# darwin-radio.net
KiCad netlist of a schematic drawn in EAGLE
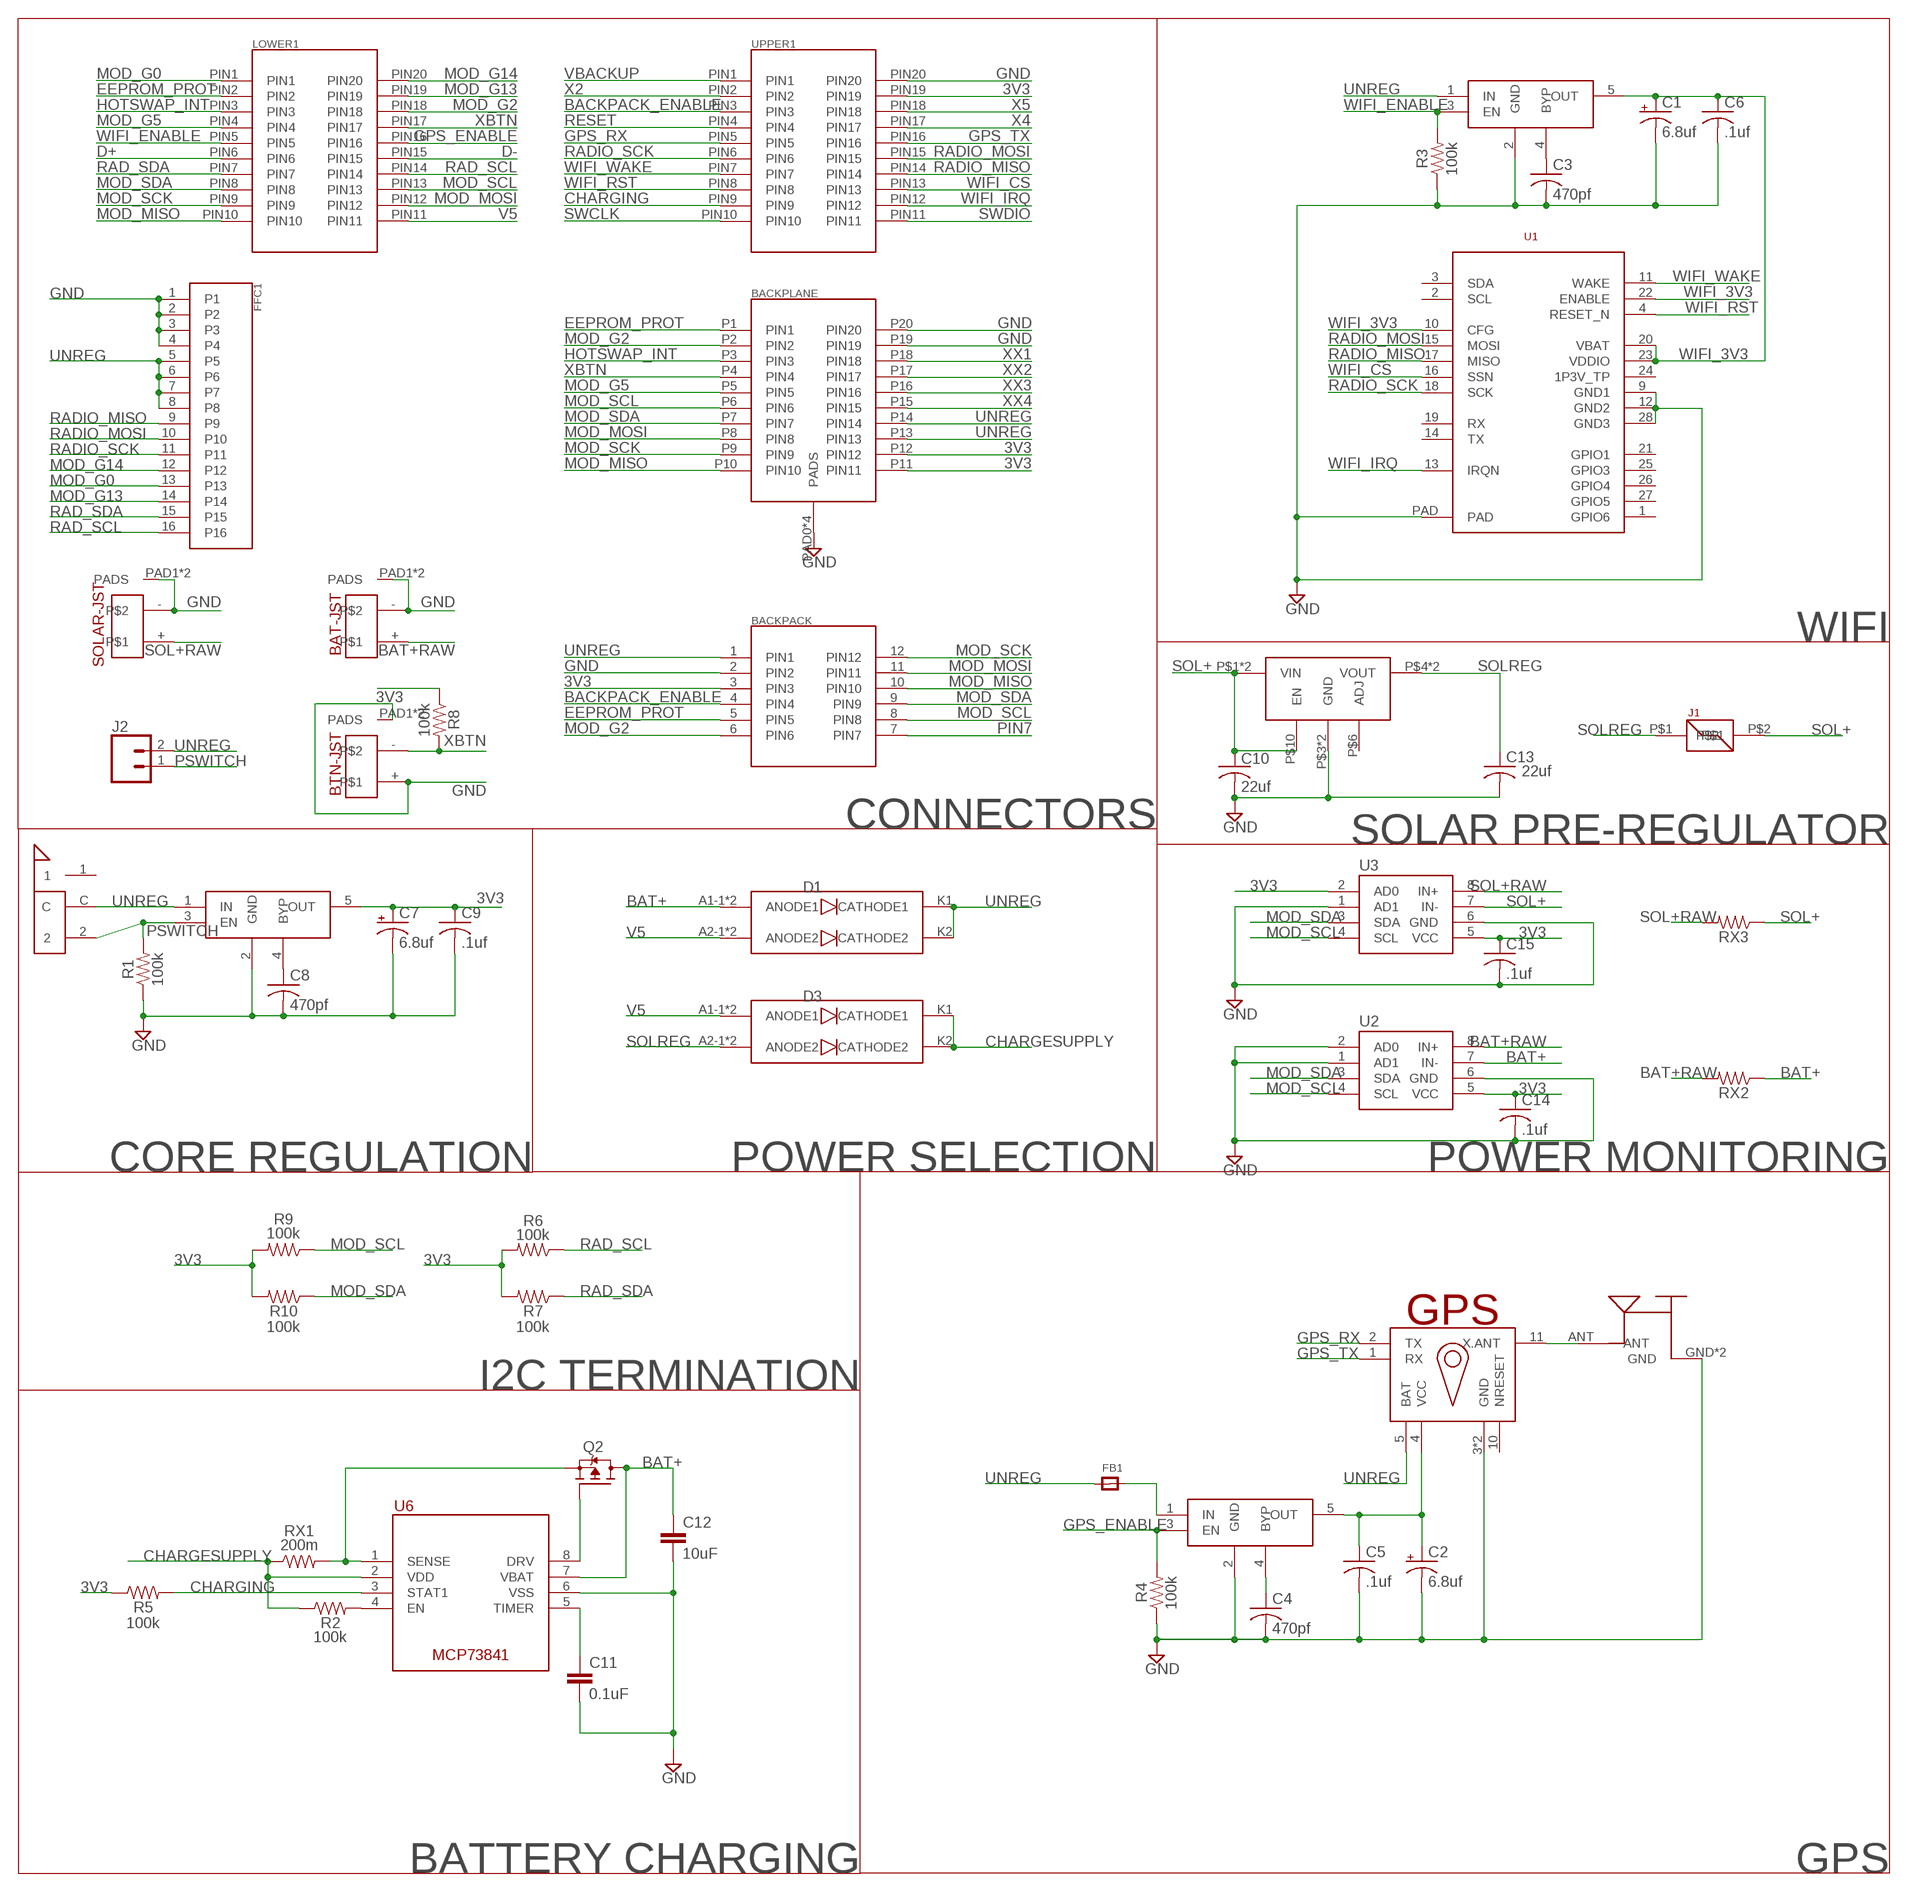
[diagram p0: schematic, sheet 1]

(export (version "E")
  (design (tool "Eeschema 10.0.6"))
  (components
    (comp (ref "BACKPACK")
      (value "2X6-HEADERSDS")
      (footprint "eagle-import:12PH")
      (libsource (lib "eagle-import") (part "2X6-HEADERSDS"))
    )
    (comp (ref "BACKPLANE")
      (value "M55-6102042R")
      (footprint "eagle-import:M55-6102042R")
      (libsource (lib "eagle-import") (part "M55-6102042R"))
    )
    (comp (ref "BAT-JST")
      (value "B2B-PH-SM4-TB")
      (footprint "eagle-import:B2B-PH-SM4-TB")
      (libsource (lib "eagle-import") (part "B2B-PH-SM4-TB"))
    )
    (comp (ref "BTN-JST")
      (value "B2B-PH-SM4-TB")
      (footprint "eagle-import:B2B-PH-SM4-TB")
      (libsource (lib "eagle-import") (part "B2B-PH-SM4-TB"))
    )
    (comp (ref "C1")
      (value "6.8uf")
      (footprint "eagle-import:A_3216-18R")
      (libsource (lib "eagle-import") (part "CPOL-USA/3216-18R"))
    )
    (comp (ref "C2")
      (value "6.8uf")
      (footprint "eagle-import:A_3216-18R")
      (libsource (lib "eagle-import") (part "CPOL-USA/3216-18R"))
    )
    (comp (ref "C3")
      (value "470pf")
      (footprint "eagle-import:C0603K")
      (libsource (lib "eagle-import") (part "C-USC0603K"))
    )
    (comp (ref "C4")
      (value "470pf")
      (footprint "eagle-import:C0603K")
      (libsource (lib "eagle-import") (part "C-USC0603K"))
    )
    (comp (ref "C5")
      (value ".1uf")
      (footprint "eagle-import:C0603K")
      (libsource (lib "eagle-import") (part "C-USC0603K"))
    )
    (comp (ref "C6")
      (value ".1uf")
      (footprint "eagle-import:C0603K")
      (libsource (lib "eagle-import") (part "C-USC0603K"))
    )
    (comp (ref "C7")
      (value "6.8uf")
      (footprint "eagle-import:A_3216-18R")
      (libsource (lib "eagle-import") (part "CPOL-USA/3216-18R"))
    )
    (comp (ref "C8")
      (value "470pf")
      (footprint "eagle-import:C0603K")
      (libsource (lib "eagle-import") (part "C-USC0603K"))
    )
    (comp (ref "C9")
      (value ".1uf")
      (footprint "eagle-import:C0603K")
      (libsource (lib "eagle-import") (part "C-USC0603K"))
    )
    (comp (ref "C10")
      (value "22uf")
      (footprint "eagle-import:C0603K")
      (libsource (lib "eagle-import") (part "C-USC0603K"))
    )
    (comp (ref "C11")
      (value "0.1uF")
      (footprint "eagle-import:0603")
      (libsource (lib "eagle-import") (part "0.1UF-0603-25V-(+80/-20%)"))
    )
    (comp (ref "C12")
      (value "10uF")
      (footprint "eagle-import:0603")
      (libsource (lib "eagle-import") (part "10UF-0603-6.3V-20%"))
    )
    (comp (ref "C13")
      (value "22uf")
      (footprint "eagle-import:C0603K")
      (libsource (lib "eagle-import") (part "C-USC0603K"))
    )
    (comp (ref "C14")
      (value ".1uf")
      (footprint "eagle-import:C0603K")
      (libsource (lib "eagle-import") (part "C-USC0603K"))
    )
    (comp (ref "C15")
      (value ".1uf")
      (footprint "eagle-import:C0603K")
      (libsource (lib "eagle-import") (part "C-USC0603K"))
    )
    (comp (ref "D1")
      (value "V10KL45DUHM3/H")
      (footprint "eagle-import:V10KL45DUHM3_H")
      (libsource (lib "eagle-import") (part "V10KL45DUHM3/H"))
    )
    (comp (ref "D3")
      (value "V10KL45DUHM3/H")
      (footprint "eagle-import:V10KL45DUHM3_H")
      (libsource (lib "eagle-import") (part "V10KL45DUHM3/H"))
    )
    (comp (ref "FB1")
      (value "FERRITE0805")
      (footprint "eagle-import:0805")
      (libsource (lib "eagle-import") (part "FERRITE0805"))
    )
    (comp (ref "FFC1")
      (value "505110-1692")
      (footprint "eagle-import:505110-1692")
      (libsource (lib "eagle-import") (part "505110-1692"))
    )
    (comp (ref "J1")
      (value "S1911-46R")
      (footprint "eagle-import:S1911-46R")
      (libsource (lib "eagle-import") (part "S1911-46R"))
    )
    (comp (ref "J2")
      (value "CONN_02LOCK_LONGPADS")
      (footprint "eagle-import:1X02_LOCK_LONGPADS")
      (libsource (lib "eagle-import") (part "CONN_02LOCK_LONGPADS"))
    )
    (comp (ref "LOWER1")
      (value "MOLEX-15-91-2200")
      (footprint "eagle-import:20PH")
      (libsource (lib "eagle-import") (part "MOLEX-15-91-2200"))
    )
    (comp (ref "Q2")
      (value "NDS8434")
      (footprint "eagle-import:SO08-IRF")
      (libsource (lib "eagle-import") (part "NDS8434"))
    )
    (comp (ref "R1")
      (value "100k")
      (footprint "eagle-import:0603")
      (libsource (lib "eagle-import") (part "100KOHM-0603-1/10W-1%"))
    )
    (comp (ref "R2")
      (value "100k")
      (footprint "eagle-import:0603")
      (libsource (lib "eagle-import") (part "100KOHM-0603-1/10W-1%"))
    )
    (comp (ref "R3")
      (value "100k")
      (footprint "eagle-import:0603")
      (libsource (lib "eagle-import") (part "100KOHM-0603-1/10W-1%"))
    )
    (comp (ref "R4")
      (value "100k")
      (footprint "eagle-import:0603")
      (libsource (lib "eagle-import") (part "100KOHM-0603-1/10W-1%"))
    )
    (comp (ref "R5")
      (value "100k")
      (footprint "eagle-import:0603")
      (libsource (lib "eagle-import") (part "100KOHM-0603-1/10W-1%"))
    )
    (comp (ref "R6")
      (value "100k")
      (footprint "eagle-import:0603")
      (libsource (lib "eagle-import") (part "100KOHM-0603-1/10W-1%"))
    )
    (comp (ref "R7")
      (value "100k")
      (footprint "eagle-import:0603")
      (libsource (lib "eagle-import") (part "100KOHM-0603-1/10W-1%"))
    )
    (comp (ref "R8")
      (value "100k")
      (footprint "eagle-import:0603")
      (libsource (lib "eagle-import") (part "100KOHM-0603-1/10W-1%"))
    )
    (comp (ref "R9")
      (value "100k")
      (footprint "eagle-import:0603")
      (libsource (lib "eagle-import") (part "100KOHM-0603-1/10W-1%"))
    )
    (comp (ref "R10")
      (value "100k")
      (footprint "eagle-import:0603")
      (libsource (lib "eagle-import") (part "100KOHM-0603-1/10W-1%"))
    )
    (comp (ref "REG1")
      (value "V78E06-1000-SMT-TR")
      (footprint "eagle-import:V78E06-1000-SMT-TR")
      (libsource (lib "eagle-import") (part "V78E06-1000-SMT-TR"))
    )
    (comp (ref "RX1")
      (value "200m")
      (footprint "eagle-import:R2512")
      (libsource (lib "eagle-import") (part "R-US_R2512"))
    )
    (comp (ref "RX2")
      (value "100M")
      (footprint "eagle-import:R2512")
      (libsource (lib "eagle-import") (part "R-US_R2512"))
    )
    (comp (ref "RX3")
      (value "100M")
      (footprint "eagle-import:R2512")
      (libsource (lib "eagle-import") (part "R-US_R2512"))
    )
    (comp (ref "SOLAR-JST")
      (value "B2B-PH-SM4-TB")
      (footprint "eagle-import:B2B-PH-SM4-TB")
      (libsource (lib "eagle-import") (part "B2B-PH-SM4-TB"))
    )
    (comp (ref "U$1")
      (value "FGPMMOPA6HL80")
      (footprint "eagle-import:L80-M39")
      (libsource (lib "eagle-import") (part "FGPMMOPA6HL80"))
    )
    (comp (ref "U$2")
      (value "MIC5219-3.3YM5-TR")
      (footprint "eagle-import:SOT95P280X145-5")
      (libsource (lib "eagle-import") (part "MIC5219-3.3YM5-TR"))
    )
    (comp (ref "U$3")
      (value "MIC5219-3.3YM5-TR")
      (footprint "eagle-import:SOT95P280X145-5")
      (libsource (lib "eagle-import") (part "MIC5219-3.3YM5-TR"))
    )
    (comp (ref "U$4")
      (value "MIC5219-3.3YM5-TR")
      (footprint "eagle-import:SOT95P280X145-5")
      (libsource (lib "eagle-import") (part "MIC5219-3.3YM5-TR"))
    )
    (comp (ref "U$5")
      (value "SSAJ110100")
      (footprint "eagle-import:SSAJ110100")
      (libsource (lib "eagle-import") (part "SSAJ110100"))
    )
    (comp (ref "U$11")
      (value "2337019-1")
      (footprint "eagle-import:2337019-1")
      (libsource (lib "eagle-import") (part "2337019-1"))
    )
    (comp (ref "U1")
      (value "ATWINC")
      (footprint "eagle-import:ATWINC")
      (libsource (lib "eagle-import") (part "ATWINC"))
    )
    (comp (ref "U2")
      (value "INA219")
      (footprint "eagle-import:SOIC127P599X175-8N")
      (libsource (lib "eagle-import") (part "INA219"))
    )
    (comp (ref "U3")
      (value "INA219")
      (footprint "eagle-import:SOIC127P599X175-8N")
      (libsource (lib "eagle-import") (part "INA219"))
    )
    (comp (ref "U6")
      (value "MCP7384X")
      (footprint "eagle-import:SOP65P490X110-8")
      (libsource (lib "eagle-import") (part "MCP7384X"))
    )
    (comp (ref "UPPER1")
      (value "MOLEX-15-91-2200")
      (footprint "eagle-import:20PH")
      (libsource (lib "eagle-import") (part "MOLEX-15-91-2200"))
    )
  )
  (nets
    (net (code "1") (name "/3V3") (class "Default")
      (node (ref "BACKPACK") (pin "3") (pinfunction "PIN3_3") (pintype "bidirectional"))
      (node (ref "BACKPLANE") (pin "P11") (pinfunction "PIN11_P11") (pintype "bidirectional"))
      (node (ref "BACKPLANE") (pin "P12") (pinfunction "PIN12_P12") (pintype "bidirectional"))
      (node (ref "C14") (pin "1") (pinfunction "1_1") (pintype "passive"))
      (node (ref "C15") (pin "1") (pinfunction "1_1") (pintype "passive"))
      (node (ref "C7") (pin "+") (pinfunction "+_+") (pintype "passive"))
      (node (ref "C9") (pin "1") (pinfunction "1_1") (pintype "passive"))
      (node (ref "R10") (pin "2") (pinfunction "2_2") (pintype "passive"))
      (node (ref "R5") (pin "1") (pinfunction "1_1") (pintype "passive"))
      (node (ref "R6") (pin "2") (pinfunction "2_2") (pintype "passive"))
      (node (ref "R7") (pin "2") (pinfunction "2_2") (pintype "passive"))
      (node (ref "R8") (pin "1") (pinfunction "1_1") (pintype "passive"))
      (node (ref "R9") (pin "2") (pinfunction "2_2") (pintype "passive"))
      (node (ref "U$4") (pin "5") (pinfunction "OUT_5") (pintype "bidirectional"))
      (node (ref "U2") (pin "5") (pinfunction "VCC_5") (pintype "bidirectional"))
      (node (ref "U3") (pin "2") (pinfunction "AD0_2") (pintype "bidirectional"))
      (node (ref "U3") (pin "5") (pinfunction "VCC_5") (pintype "bidirectional"))
      (node (ref "UPPER1") (pin "PIN19") (pinfunction "PIN19_PIN19") (pintype "bidirectional"))
    )
    (net (code "2") (name "/BACKPACK_ENABLE") (class "Default")
      (node (ref "BACKPACK") (pin "4") (pinfunction "PIN4_4") (pintype "bidirectional"))
      (node (ref "UPPER1") (pin "PIN3") (pinfunction "PIN3_PIN3") (pintype "bidirectional"))
    )
    (net (code "3") (name "/BAT+") (class "Default")
      (node (ref "C12") (pin "1") (pinfunction "1_1") (pintype "passive"))
      (node (ref "D1") (pin "A1-1") (pinfunction "ANODE1_A1-1") (pintype "bidirectional"))
      (node (ref "D1") (pin "A1-2") (pinfunction "ANODE1_A1-2") (pintype "bidirectional"))
      (node (ref "Q2") (pin "5") (pinfunction "D_5") (pintype "passive"))
      (node (ref "Q2") (pin "6") (pinfunction "D_6") (pintype "passive"))
      (node (ref "Q2") (pin "7") (pinfunction "D_7") (pintype "passive"))
      (node (ref "Q2") (pin "8") (pinfunction "D_8") (pintype "passive"))
      (node (ref "RX2") (pin "1") (pinfunction "1_1") (pintype "passive"))
      (node (ref "U2") (pin "7") (pinfunction "IN-_7") (pintype "bidirectional"))
      (node (ref "U6") (pin "7") (pinfunction "VBAT_7") (pintype "bidirectional"))
    )
    (net (code "4") (name "/BAT+RAW") (class "Default")
      (node (ref "BAT-JST") (pin "+") (pinfunction "P$1_+") (pintype "bidirectional"))
      (node (ref "RX2") (pin "2") (pinfunction "2_2") (pintype "passive"))
      (node (ref "U2") (pin "8") (pinfunction "IN+_8") (pintype "bidirectional"))
    )
    (net (code "5") (name "/CHARGESUPPLY") (class "Default")
      (node (ref "D3") (pin "K1") (pinfunction "CATHODE1_K1") (pintype "bidirectional"))
      (node (ref "D3") (pin "K2") (pinfunction "CATHODE2_K2") (pintype "bidirectional"))
      (node (ref "R2") (pin "1") (pinfunction "1_1") (pintype "passive"))
      (node (ref "RX1") (pin "1") (pinfunction "1_1") (pintype "passive"))
      (node (ref "U6") (pin "2") (pinfunction "VDD_2") (pintype "bidirectional"))
    )
    (net (code "6") (name "/CHARGING") (class "Default")
      (node (ref "R5") (pin "2") (pinfunction "2_2") (pintype "passive"))
      (node (ref "U6") (pin "3") (pinfunction "STAT1_3") (pintype "bidirectional"))
      (node (ref "UPPER1") (pin "PIN9") (pinfunction "PIN9_PIN9") (pintype "bidirectional"))
    )
    (net (code "7") (name "/D+") (class "Default")
      (node (ref "LOWER1") (pin "PIN6") (pinfunction "PIN6_PIN6") (pintype "bidirectional"))
    )
    (net (code "8") (name "/D-") (class "Default")
      (node (ref "LOWER1") (pin "PIN15") (pinfunction "PIN15_PIN15") (pintype "bidirectional"))
    )
    (net (code "9") (name "/EEPROM_PROT") (class "Default")
      (node (ref "BACKPACK") (pin "5") (pinfunction "PIN5_5") (pintype "bidirectional"))
      (node (ref "BACKPLANE") (pin "P1") (pinfunction "PIN1_P1") (pintype "bidirectional"))
      (node (ref "LOWER1") (pin "PIN2") (pinfunction "PIN2_PIN2") (pintype "bidirectional"))
    )
    (net (code "10") (name "/GPS_ENABLE") (class "Default")
      (node (ref "LOWER1") (pin "PIN16") (pinfunction "PIN16_PIN16") (pintype "bidirectional"))
      (node (ref "R4") (pin "2") (pinfunction "2_2") (pintype "passive"))
      (node (ref "U$2") (pin "3") (pinfunction "EN_3") (pintype "bidirectional"))
    )
    (net (code "11") (name "/GPS_RX") (class "Default")
      (node (ref "U$1") (pin "2") (pinfunction "TX_2") (pintype "bidirectional"))
      (node (ref "UPPER1") (pin "PIN5") (pinfunction "PIN5_PIN5") (pintype "bidirectional"))
    )
    (net (code "12") (name "/GPS_TX") (class "Default")
      (node (ref "U$1") (pin "1") (pinfunction "RX_1") (pintype "bidirectional"))
      (node (ref "UPPER1") (pin "PIN16") (pinfunction "PIN16_PIN16") (pintype "bidirectional"))
    )
    (net (code "13") (name "/HOTSWAP_INT") (class "Default")
      (node (ref "BACKPLANE") (pin "P3") (pinfunction "PIN3_P3") (pintype "bidirectional"))
      (node (ref "LOWER1") (pin "PIN3") (pinfunction "PIN3_PIN3") (pintype "bidirectional"))
    )
    (net (code "14") (name "/MOD_G0") (class "Default")
      (node (ref "FFC1") (pin "13") (pinfunction "P13_13") (pintype "bidirectional"))
      (node (ref "LOWER1") (pin "PIN1") (pinfunction "PIN1_PIN1") (pintype "bidirectional"))
    )
    (net (code "15") (name "/MOD_G2") (class "Default")
      (node (ref "BACKPACK") (pin "6") (pinfunction "PIN6_6") (pintype "bidirectional"))
      (node (ref "BACKPLANE") (pin "P2") (pinfunction "PIN2_P2") (pintype "bidirectional"))
      (node (ref "LOWER1") (pin "PIN18") (pinfunction "PIN18_PIN18") (pintype "bidirectional"))
    )
    (net (code "16") (name "/MOD_G5") (class "Default")
      (node (ref "BACKPLANE") (pin "P5") (pinfunction "PIN5_P5") (pintype "bidirectional"))
      (node (ref "LOWER1") (pin "PIN4") (pinfunction "PIN4_PIN4") (pintype "bidirectional"))
    )
    (net (code "17") (name "/MOD_G13") (class "Default")
      (node (ref "FFC1") (pin "14") (pinfunction "P14_14") (pintype "bidirectional"))
      (node (ref "LOWER1") (pin "PIN19") (pinfunction "PIN19_PIN19") (pintype "bidirectional"))
    )
    (net (code "18") (name "/MOD_G14") (class "Default")
      (node (ref "FFC1") (pin "12") (pinfunction "P12_12") (pintype "bidirectional"))
      (node (ref "LOWER1") (pin "PIN20") (pinfunction "PIN20_PIN20") (pintype "bidirectional"))
    )
    (net (code "19") (name "/MOD_MISO") (class "Default")
      (node (ref "BACKPACK") (pin "10") (pinfunction "PIN10_10") (pintype "bidirectional"))
      (node (ref "BACKPLANE") (pin "P10") (pinfunction "PIN10_P10") (pintype "bidirectional"))
      (node (ref "LOWER1") (pin "PIN10") (pinfunction "PIN10_PIN10") (pintype "bidirectional"))
    )
    (net (code "20") (name "/MOD_MOSI") (class "Default")
      (node (ref "BACKPACK") (pin "11") (pinfunction "PIN11_11") (pintype "bidirectional"))
      (node (ref "BACKPLANE") (pin "P8") (pinfunction "PIN8_P8") (pintype "bidirectional"))
      (node (ref "LOWER1") (pin "PIN12") (pinfunction "PIN12_PIN12") (pintype "bidirectional"))
    )
    (net (code "21") (name "/MOD_SCK") (class "Default")
      (node (ref "BACKPACK") (pin "12") (pinfunction "PIN12_12") (pintype "bidirectional"))
      (node (ref "BACKPLANE") (pin "P9") (pinfunction "PIN9_P9") (pintype "bidirectional"))
      (node (ref "LOWER1") (pin "PIN9") (pinfunction "PIN9_PIN9") (pintype "bidirectional"))
    )
    (net (code "22") (name "/MOD_SCL") (class "Default")
      (node (ref "BACKPACK") (pin "8") (pinfunction "PIN8_8") (pintype "bidirectional"))
      (node (ref "BACKPLANE") (pin "P6") (pinfunction "PIN6_P6") (pintype "bidirectional"))
      (node (ref "LOWER1") (pin "PIN13") (pinfunction "PIN13_PIN13") (pintype "bidirectional"))
      (node (ref "R9") (pin "1") (pinfunction "1_1") (pintype "passive"))
      (node (ref "U2") (pin "4") (pinfunction "SCL_4") (pintype "bidirectional"))
      (node (ref "U3") (pin "4") (pinfunction "SCL_4") (pintype "bidirectional"))
    )
    (net (code "23") (name "/MOD_SDA") (class "Default")
      (node (ref "BACKPACK") (pin "9") (pinfunction "PIN9_9") (pintype "bidirectional"))
      (node (ref "BACKPLANE") (pin "P7") (pinfunction "PIN7_P7") (pintype "bidirectional"))
      (node (ref "LOWER1") (pin "PIN8") (pinfunction "PIN8_PIN8") (pintype "bidirectional"))
      (node (ref "R10") (pin "1") (pinfunction "1_1") (pintype "passive"))
      (node (ref "U2") (pin "3") (pinfunction "SDA_3") (pintype "bidirectional"))
      (node (ref "U3") (pin "3") (pinfunction "SDA_3") (pintype "bidirectional"))
    )
    (net (code "24") (name "/PIN7") (class "Default")
      (node (ref "BACKPACK") (pin "7") (pinfunction "PIN7_7") (pintype "bidirectional"))
    )
    (net (code "25") (name "/PSWITCH") (class "Default")
      (node (ref "J2") (pin "1") (pinfunction "1_1") (pintype "passive"))
      (node (ref "R1") (pin "2") (pinfunction "2_2") (pintype "passive"))
      (node (ref "U$4") (pin "3") (pinfunction "EN_3") (pintype "bidirectional"))
      (node (ref "U$5") (pin "2") (pinfunction "2_2") (pintype "bidirectional"))
    )
    (net (code "26") (name "/RADIO_MISO") (class "Default")
      (node (ref "FFC1") (pin "9") (pinfunction "P9_9") (pintype "bidirectional"))
      (node (ref "U1") (pin "17") (pinfunction "MISO_17") (pintype "bidirectional"))
      (node (ref "UPPER1") (pin "PIN14") (pinfunction "PIN14_PIN14") (pintype "bidirectional"))
    )
    (net (code "27") (name "/RADIO_MOSI") (class "Default")
      (node (ref "FFC1") (pin "10") (pinfunction "P10_10") (pintype "bidirectional"))
      (node (ref "U1") (pin "15") (pinfunction "MOSI_15") (pintype "bidirectional"))
      (node (ref "UPPER1") (pin "PIN15") (pinfunction "PIN15_PIN15") (pintype "bidirectional"))
    )
    (net (code "28") (name "/RADIO_SCK") (class "Default")
      (node (ref "FFC1") (pin "11") (pinfunction "P11_11") (pintype "bidirectional"))
      (node (ref "U1") (pin "18") (pinfunction "SCK_18") (pintype "bidirectional"))
      (node (ref "UPPER1") (pin "PIN6") (pinfunction "PIN6_PIN6") (pintype "bidirectional"))
    )
    (net (code "29") (name "/RAD_SCL") (class "Default")
      (node (ref "FFC1") (pin "16") (pinfunction "P16_16") (pintype "bidirectional"))
      (node (ref "LOWER1") (pin "PIN14") (pinfunction "PIN14_PIN14") (pintype "bidirectional"))
      (node (ref "R6") (pin "1") (pinfunction "1_1") (pintype "passive"))
    )
    (net (code "30") (name "/RAD_SDA") (class "Default")
      (node (ref "FFC1") (pin "15") (pinfunction "P15_15") (pintype "bidirectional"))
      (node (ref "LOWER1") (pin "PIN7") (pinfunction "PIN7_PIN7") (pintype "bidirectional"))
      (node (ref "R7") (pin "1") (pinfunction "1_1") (pintype "passive"))
    )
    (net (code "31") (name "/RESET") (class "Default")
      (node (ref "UPPER1") (pin "PIN4") (pinfunction "PIN4_PIN4") (pintype "bidirectional"))
    )
    (net (code "32") (name "/SOL+") (class "Default")
      (node (ref "C10") (pin "1") (pinfunction "1_1") (pintype "passive"))
      (node (ref "J1") (pin "P$2") (pinfunction "P$2_P$2") (pintype "bidirectional"))
      (node (ref "REG1") (pin "P$1") (pinfunction "VIN_P$1") (pintype "bidirectional"))
      (node (ref "REG1") (pin "P$10") (pinfunction "EN_P$10") (pintype "bidirectional"))
      (node (ref "REG1") (pin "P$2") (pinfunction "VIN_P$2") (pintype "bidirectional"))
      (node (ref "RX3") (pin "1") (pinfunction "1_1") (pintype "passive"))
      (node (ref "U3") (pin "7") (pinfunction "IN-_7") (pintype "bidirectional"))
    )
    (net (code "33") (name "/SOL+RAW") (class "Default")
      (node (ref "RX3") (pin "2") (pinfunction "2_2") (pintype "passive"))
      (node (ref "SOLAR-JST") (pin "+") (pinfunction "P$1_+") (pintype "bidirectional"))
      (node (ref "U3") (pin "8") (pinfunction "IN+_8") (pintype "bidirectional"))
    )
    (net (code "34") (name "/SOLREG") (class "Default")
      (node (ref "C13") (pin "1") (pinfunction "1_1") (pintype "passive"))
      (node (ref "D3") (pin "A2-1") (pinfunction "ANODE2_A2-1") (pintype "bidirectional"))
      (node (ref "D3") (pin "A2-2") (pinfunction "ANODE2_A2-2") (pintype "bidirectional"))
      (node (ref "J1") (pin "P$1") (pinfunction "P$1_P$1") (pintype "bidirectional"))
      (node (ref "REG1") (pin "P$4") (pinfunction "VOUT_P$4") (pintype "bidirectional"))
      (node (ref "REG1") (pin "P$5") (pinfunction "VOUT_P$5") (pintype "bidirectional"))
    )
    (net (code "35") (name "/SWCLK") (class "Default")
      (node (ref "UPPER1") (pin "PIN10") (pinfunction "PIN10_PIN10") (pintype "bidirectional"))
    )
    (net (code "36") (name "/SWDIO") (class "Default")
      (node (ref "UPPER1") (pin "PIN11") (pinfunction "PIN11_PIN11") (pintype "bidirectional"))
    )
    (net (code "37") (name "/UNREG") (class "Default")
      (node (ref "BACKPACK") (pin "1") (pinfunction "PIN1_1") (pintype "bidirectional"))
      (node (ref "BACKPLANE") (pin "P13") (pinfunction "PIN13_P13") (pintype "bidirectional"))
      (node (ref "BACKPLANE") (pin "P14") (pinfunction "PIN14_P14") (pintype "bidirectional"))
      (node (ref "D1") (pin "K1") (pinfunction "CATHODE1_K1") (pintype "bidirectional"))
      (node (ref "D1") (pin "K2") (pinfunction "CATHODE2_K2") (pintype "bidirectional"))
      (node (ref "FB1") (pin "1") (pinfunction "P$1_1") (pintype "passive"))
      (node (ref "FFC1") (pin "5") (pinfunction "P5_5") (pintype "bidirectional"))
      (node (ref "FFC1") (pin "6") (pinfunction "P6_6") (pintype "bidirectional"))
      (node (ref "FFC1") (pin "7") (pinfunction "P7_7") (pintype "bidirectional"))
      (node (ref "FFC1") (pin "8") (pinfunction "P8_8") (pintype "bidirectional"))
      (node (ref "J2") (pin "2") (pinfunction "2_2") (pintype "passive"))
      (node (ref "U$1") (pin "5") (pinfunction "BAT_5") (pintype "bidirectional"))
      (node (ref "U$3") (pin "1") (pinfunction "IN_1") (pintype "bidirectional"))
      (node (ref "U$4") (pin "1") (pinfunction "IN_1") (pintype "bidirectional"))
      (node (ref "U$5") (pin "C") (pinfunction "C_C") (pintype "bidirectional"))
    )
    (net (code "38") (name "/V5") (class "Default")
      (node (ref "D1") (pin "A2-1") (pinfunction "ANODE2_A2-1") (pintype "bidirectional"))
      (node (ref "D1") (pin "A2-2") (pinfunction "ANODE2_A2-2") (pintype "bidirectional"))
      (node (ref "D3") (pin "A1-1") (pinfunction "ANODE1_A1-1") (pintype "bidirectional"))
      (node (ref "D3") (pin "A1-2") (pinfunction "ANODE1_A1-2") (pintype "bidirectional"))
      (node (ref "LOWER1") (pin "PIN11") (pinfunction "PIN11_PIN11") (pintype "bidirectional"))
    )
    (net (code "39") (name "/VBACKUP") (class "Default")
      (node (ref "UPPER1") (pin "PIN1") (pinfunction "PIN1_PIN1") (pintype "bidirectional"))
    )
    (net (code "40") (name "/WIFI_3V3") (class "Default")
      (node (ref "C1") (pin "+") (pinfunction "+_+") (pintype "passive"))
      (node (ref "C6") (pin "1") (pinfunction "1_1") (pintype "passive"))
      (node (ref "U$3") (pin "5") (pinfunction "OUT_5") (pintype "bidirectional"))
      (node (ref "U1") (pin "10") (pinfunction "CFG_10") (pintype "bidirectional"))
      (node (ref "U1") (pin "20") (pinfunction "VBAT_20") (pintype "bidirectional"))
      (node (ref "U1") (pin "22") (pinfunction "ENABLE_22") (pintype "bidirectional"))
      (node (ref "U1") (pin "23") (pinfunction "VDDIO_23") (pintype "bidirectional"))
    )
    (net (code "41") (name "/WIFI_CS") (class "Default")
      (node (ref "U1") (pin "16") (pinfunction "SSN_16") (pintype "bidirectional"))
      (node (ref "UPPER1") (pin "PIN13") (pinfunction "PIN13_PIN13") (pintype "bidirectional"))
    )
    (net (code "42") (name "/WIFI_ENABLE") (class "Default")
      (node (ref "LOWER1") (pin "PIN5") (pinfunction "PIN5_PIN5") (pintype "bidirectional"))
      (node (ref "R3") (pin "2") (pinfunction "2_2") (pintype "passive"))
      (node (ref "U$3") (pin "3") (pinfunction "EN_3") (pintype "bidirectional"))
    )
    (net (code "43") (name "/WIFI_IRQ") (class "Default")
      (node (ref "U1") (pin "13") (pinfunction "IRQN_13") (pintype "bidirectional"))
      (node (ref "UPPER1") (pin "PIN12") (pinfunction "PIN12_PIN12") (pintype "bidirectional"))
    )
    (net (code "44") (name "/WIFI_RST") (class "Default")
      (node (ref "U1") (pin "4") (pinfunction "RESET_N_4") (pintype "bidirectional"))
      (node (ref "UPPER1") (pin "PIN8") (pinfunction "PIN8_PIN8") (pintype "bidirectional"))
    )
    (net (code "45") (name "/WIFI_WAKE") (class "Default")
      (node (ref "U1") (pin "11") (pinfunction "WAKE_11") (pintype "bidirectional"))
      (node (ref "UPPER1") (pin "PIN7") (pinfunction "PIN7_PIN7") (pintype "bidirectional"))
    )
    (net (code "46") (name "/X2") (class "Default")
      (node (ref "UPPER1") (pin "PIN2") (pinfunction "PIN2_PIN2") (pintype "bidirectional"))
    )
    (net (code "47") (name "/X4") (class "Default")
      (node (ref "UPPER1") (pin "PIN17") (pinfunction "PIN17_PIN17") (pintype "bidirectional"))
    )
    (net (code "48") (name "/X5") (class "Default")
      (node (ref "UPPER1") (pin "PIN18") (pinfunction "PIN18_PIN18") (pintype "bidirectional"))
    )
    (net (code "49") (name "/XBTN") (class "Default")
      (node (ref "BACKPLANE") (pin "P4") (pinfunction "PIN4_P4") (pintype "bidirectional"))
      (node (ref "BTN-JST") (pin "-") (pinfunction "P$2_-") (pintype "bidirectional"))
      (node (ref "LOWER1") (pin "PIN17") (pinfunction "PIN17_PIN17") (pintype "bidirectional"))
      (node (ref "R8") (pin "2") (pinfunction "2_2") (pintype "passive"))
    )
    (net (code "50") (name "/XX1") (class "Default")
      (node (ref "BACKPLANE") (pin "P18") (pinfunction "PIN18_P18") (pintype "bidirectional"))
    )
    (net (code "51") (name "/XX2") (class "Default")
      (node (ref "BACKPLANE") (pin "P17") (pinfunction "PIN17_P17") (pintype "bidirectional"))
    )
    (net (code "52") (name "/XX3") (class "Default")
      (node (ref "BACKPLANE") (pin "P16") (pinfunction "PIN16_P16") (pintype "bidirectional"))
    )
    (net (code "53") (name "/XX4") (class "Default")
      (node (ref "BACKPLANE") (pin "P15") (pinfunction "PIN15_P15") (pintype "bidirectional"))
    )
    (net (code "54") (name "GND") (class "Default")
      (node (ref "BACKPACK") (pin "2") (pinfunction "PIN2_2") (pintype "bidirectional"))
      (node (ref "BACKPLANE") (pin "P19") (pinfunction "PIN19_P19") (pintype "bidirectional"))
      (node (ref "BACKPLANE") (pin "P20") (pinfunction "PIN20_P20") (pintype "bidirectional"))
      (node (ref "BACKPLANE") (pin "PAD0") (pinfunction "PADS_PAD0") (pintype "bidirectional"))
      (node (ref "BACKPLANE") (pin "PAD1") (pinfunction "PADS_PAD1") (pintype "bidirectional"))
      (node (ref "BACKPLANE") (pin "PAD2") (pinfunction "PADS_PAD2") (pintype "bidirectional"))
      (node (ref "BACKPLANE") (pin "PAD3") (pinfunction "PADS_PAD3") (pintype "bidirectional"))
      (node (ref "BAT-JST") (pin "-") (pinfunction "P$2_-") (pintype "bidirectional"))
      (node (ref "BAT-JST") (pin "PAD1") (pinfunction "PADS_PAD1") (pintype "bidirectional"))
      (node (ref "BAT-JST") (pin "PAD2") (pinfunction "PADS_PAD2") (pintype "bidirectional"))
      (node (ref "BTN-JST") (pin "+") (pinfunction "P$1_+") (pintype "bidirectional"))
      (node (ref "BTN-JST") (pin "PAD1") (pinfunction "PADS_PAD1") (pintype "bidirectional"))
      (node (ref "BTN-JST") (pin "PAD2") (pinfunction "PADS_PAD2") (pintype "bidirectional"))
      (node (ref "C1") (pin "-") (pinfunction "-_-") (pintype "passive"))
      (node (ref "C10") (pin "2") (pinfunction "2_2") (pintype "passive"))
      (node (ref "C11") (pin "2") (pinfunction "2_2") (pintype "passive"))
      (node (ref "C12") (pin "2") (pinfunction "2_2") (pintype "passive"))
      (node (ref "C13") (pin "2") (pinfunction "2_2") (pintype "passive"))
      (node (ref "C14") (pin "2") (pinfunction "2_2") (pintype "passive"))
      (node (ref "C15") (pin "2") (pinfunction "2_2") (pintype "passive"))
      (node (ref "C2") (pin "-") (pinfunction "-_-") (pintype "passive"))
      (node (ref "C3") (pin "2") (pinfunction "2_2") (pintype "passive"))
      (node (ref "C4") (pin "2") (pinfunction "2_2") (pintype "passive"))
      (node (ref "C5") (pin "2") (pinfunction "2_2") (pintype "passive"))
      (node (ref "C6") (pin "2") (pinfunction "2_2") (pintype "passive"))
      (node (ref "C7") (pin "-") (pinfunction "-_-") (pintype "passive"))
      (node (ref "C8") (pin "2") (pinfunction "2_2") (pintype "passive"))
      (node (ref "C9") (pin "2") (pinfunction "2_2") (pintype "passive"))
      (node (ref "FFC1") (pin "1") (pinfunction "P1_1") (pintype "bidirectional"))
      (node (ref "FFC1") (pin "2") (pinfunction "P2_2") (pintype "bidirectional"))
      (node (ref "FFC1") (pin "3") (pinfunction "P3_3") (pintype "bidirectional"))
      (node (ref "FFC1") (pin "4") (pinfunction "P4_4") (pintype "bidirectional"))
      (node (ref "R1") (pin "1") (pinfunction "1_1") (pintype "passive"))
      (node (ref "R3") (pin "1") (pinfunction "1_1") (pintype "passive"))
      (node (ref "R4") (pin "1") (pinfunction "1_1") (pintype "passive"))
      (node (ref "REG1") (pin "P$3") (pinfunction "GND_P$3") (pintype "bidirectional"))
      (node (ref "REG1") (pin "P$7") (pinfunction "GND_P$7") (pintype "bidirectional"))
      (node (ref "SOLAR-JST") (pin "-") (pinfunction "P$2_-") (pintype "bidirectional"))
      (node (ref "SOLAR-JST") (pin "PAD1") (pinfunction "PADS_PAD1") (pintype "bidirectional"))
      (node (ref "SOLAR-JST") (pin "PAD2") (pinfunction "PADS_PAD2") (pintype "bidirectional"))
      (node (ref "U$1") (pin "12") (pinfunction "GND_12") (pintype "bidirectional"))
      (node (ref "U$1") (pin "3") (pinfunction "GND_3") (pintype "bidirectional"))
      (node (ref "U$11") (pin "GND") (pinfunction "GND_GND") (pintype "bidirectional"))
      (node (ref "U$11") (pin "GND2") (pinfunction "GND_GND2") (pintype "bidirectional"))
      (node (ref "U$2") (pin "2") (pinfunction "GND_2") (pintype "bidirectional"))
      (node (ref "U$3") (pin "2") (pinfunction "GND_2") (pintype "bidirectional"))
      (node (ref "U$4") (pin "2") (pinfunction "GND_2") (pintype "bidirectional"))
      (node (ref "U1") (pin "12") (pinfunction "GND2_12") (pintype "bidirectional"))
      (node (ref "U1") (pin "28") (pinfunction "GND3_28") (pintype "bidirectional"))
      (node (ref "U1") (pin "9") (pinfunction "GND1_9") (pintype "bidirectional"))
      (node (ref "U1") (pin "PAD") (pinfunction "PAD_PAD") (pintype "bidirectional"))
      (node (ref "U2") (pin "1") (pinfunction "AD1_1") (pintype "bidirectional"))
      (node (ref "U2") (pin "2") (pinfunction "AD0_2") (pintype "bidirectional"))
      (node (ref "U2") (pin "6") (pinfunction "GND_6") (pintype "bidirectional"))
      (node (ref "U3") (pin "1") (pinfunction "AD1_1") (pintype "bidirectional"))
      (node (ref "U3") (pin "6") (pinfunction "GND_6") (pintype "bidirectional"))
      (node (ref "U6") (pin "6") (pinfunction "VSS_6") (pintype "bidirectional"))
      (node (ref "UPPER1") (pin "PIN20") (pinfunction "PIN20_PIN20") (pintype "bidirectional"))
    )
    (net (code "55") (name "Net-(FB1-P$2)") (class "Default")
      (node (ref "FB1") (pin "2") (pinfunction "P$2_2") (pintype "passive"))
      (node (ref "U$2") (pin "1") (pinfunction "IN_1") (pintype "bidirectional"))
    )
    (net (code "56") (name "Net-(Q2-G)") (class "Default")
      (node (ref "Q2") (pin "4") (pinfunction "G_4") (pintype "passive"))
      (node (ref "U6") (pin "8") (pinfunction "DRV_8") (pintype "bidirectional"))
    )
    (net (code "57") (name "Net-(U$1-VCC)") (class "Default")
      (node (ref "C2") (pin "+") (pinfunction "+_+") (pintype "passive"))
      (node (ref "C5") (pin "1") (pinfunction "1_1") (pintype "passive"))
      (node (ref "U$1") (pin "4") (pinfunction "VCC_4") (pintype "bidirectional"))
      (node (ref "U$2") (pin "5") (pinfunction "OUT_5") (pintype "bidirectional"))
    )
    (net (code "58") (name "Net-(U$1-X.ANT)") (class "Default")
      (node (ref "U$1") (pin "11") (pinfunction "X.ANT_11") (pintype "bidirectional"))
      (node (ref "U$11") (pin "ANT") (pinfunction "ANT_ANT") (pintype "bidirectional"))
    )
    (net (code "59") (name "Net-(U$2-BYP)") (class "Default")
      (node (ref "C4") (pin "1") (pinfunction "1_1") (pintype "passive"))
      (node (ref "U$2") (pin "4") (pinfunction "BYP_4") (pintype "bidirectional"))
    )
    (net (code "60") (name "Net-(U$3-BYP)") (class "Default")
      (node (ref "C3") (pin "1") (pinfunction "1_1") (pintype "passive"))
      (node (ref "U$3") (pin "4") (pinfunction "BYP_4") (pintype "bidirectional"))
    )
    (net (code "61") (name "Net-(U$4-BYP)") (class "Default")
      (node (ref "C8") (pin "1") (pinfunction "1_1") (pintype "passive"))
      (node (ref "U$4") (pin "4") (pinfunction "BYP_4") (pintype "bidirectional"))
    )
    (net (code "62") (name "Net-(U6-EN)") (class "Default")
      (node (ref "R2") (pin "2") (pinfunction "2_2") (pintype "passive"))
      (node (ref "U6") (pin "4") (pinfunction "EN_4") (pintype "bidirectional"))
    )
    (net (code "63") (name "Net-(U6-SENSE)") (class "Default")
      (node (ref "Q2") (pin "1") (pinfunction "S_1") (pintype "passive"))
      (node (ref "Q2") (pin "2") (pinfunction "S_2") (pintype "passive"))
      (node (ref "Q2") (pin "3") (pinfunction "S_3") (pintype "passive"))
      (node (ref "RX1") (pin "2") (pinfunction "2_2") (pintype "passive"))
      (node (ref "U6") (pin "1") (pinfunction "SENSE_1") (pintype "bidirectional"))
    )
    (net (code "64") (name "Net-(U6-TIMER)") (class "Default")
      (node (ref "C11") (pin "1") (pinfunction "1_1") (pintype "passive"))
      (node (ref "U6") (pin "5") (pinfunction "TIMER_5") (pintype "bidirectional"))
    )
    (net (code "65") (name "unconnected-(REG1-ADJ-PadP$6)") (class "Default")
      (node (ref "REG1") (pin "P$6") (pinfunction "ADJ_P$6") (pintype "bidirectional"))
    )
    (net (code "66") (name "unconnected-(U$1-NRESET-Pad10)") (class "Default")
      (node (ref "U$1") (pin "10") (pinfunction "NRESET_10") (pintype "bidirectional"))
    )
    (net (code "67") (name "unconnected-(U$5-Pad1)") (class "Default")
      (node (ref "U$5") (pin "1") (pinfunction "1_1") (pintype "bidirectional"))
    )
    (net (code "68") (name "unconnected-(U1-1P3V_TP-Pad24)") (class "Default")
      (node (ref "U1") (pin "24") (pinfunction "1P3V_TP_24") (pintype "bidirectional"))
    )
    (net (code "69") (name "unconnected-(U1-GPIO1-Pad21)") (class "Default")
      (node (ref "U1") (pin "21") (pinfunction "GPIO1_21") (pintype "bidirectional"))
    )
    (net (code "70") (name "unconnected-(U1-GPIO3-Pad25)") (class "Default")
      (node (ref "U1") (pin "25") (pinfunction "GPIO3_25") (pintype "bidirectional"))
    )
    (net (code "71") (name "unconnected-(U1-GPIO4-Pad26)") (class "Default")
      (node (ref "U1") (pin "26") (pinfunction "GPIO4_26") (pintype "bidirectional"))
    )
    (net (code "72") (name "unconnected-(U1-GPIO5-Pad27)") (class "Default")
      (node (ref "U1") (pin "27") (pinfunction "GPIO5_27") (pintype "bidirectional"))
    )
    (net (code "73") (name "unconnected-(U1-GPIO6-Pad1)") (class "Default")
      (node (ref "U1") (pin "1") (pinfunction "GPIO6_1") (pintype "bidirectional"))
    )
    (net (code "74") (name "unconnected-(U1-RX-Pad19)") (class "Default")
      (node (ref "U1") (pin "19") (pinfunction "RX_19") (pintype "bidirectional"))
    )
    (net (code "75") (name "unconnected-(U1-SCL-Pad2)") (class "Default")
      (node (ref "U1") (pin "2") (pinfunction "SCL_2") (pintype "bidirectional"))
    )
    (net (code "76") (name "unconnected-(U1-SDA-Pad3)") (class "Default")
      (node (ref "U1") (pin "3") (pinfunction "SDA_3") (pintype "bidirectional"))
    )
    (net (code "77") (name "unconnected-(U1-TX-Pad14)") (class "Default")
      (node (ref "U1") (pin "14") (pinfunction "TX_14") (pintype "bidirectional"))
    )
  )
)
